# Interface.net
KiCad netlist of a schematic drawn in Altium Designer
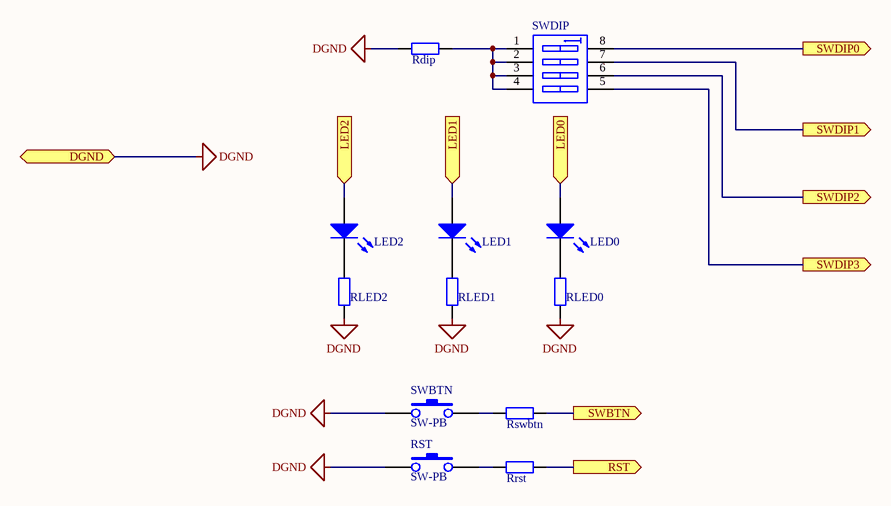
[diagram p0: Interface.SchDoc]

(export (version "E")
  (design (tool "Eeschema 10.0.6"))
  (components
    (comp (ref "LED0")
      (value "LTST-C170KGKT")
      (footprint "ECE-LED2012-0805SM")
      (description "LED GREEN CLEAR 0805 SM")
      (libsource (lib "Diodes$") (part "DIO000104"))
    )
    (comp (ref "LED1")
      (value "LTST-C170KAKT")
      (footprint "ECE-LED2012-0805SM")
      (description "LED RED ORANGE CLEAR 0805 SMD")
      (libsource (lib "Diodes$") (part "DIO000105"))
    )
    (comp (ref "LED2")
      (value "LTST-C170KAKT")
      (footprint "ECE-LED2012-0805SM")
      (description "LED RED ORANGE CLEAR 0805 SMD")
      (libsource (lib "Diodes$") (part "DIO000105"))
    )
    (comp (ref "Rdip")
      (value "1K")
      (footprint "ECE-RESC2012-0805SM")
      (description "RES CER 1K 2012 SM")
      (libsource (lib "Resistors$") (part "RES000538"))
    )
    (comp (ref "RLED0")
      (value "270R")
      (footprint "ECE-RESC1608-0603SM")
      (description "RES CER 270R 1608 SM")
      (libsource (lib "Resistors$") (part "RES000131"))
    )
    (comp (ref "RLED1")
      (value "270R")
      (footprint "ECE-RESC1608-0603SM")
      (description "RES CER 270R 1608 SM")
      (libsource (lib "Resistors$") (part "RES000131"))
    )
    (comp (ref "RLED2")
      (value "270R")
      (footprint "ECE-RESC1608-0603SM")
      (description "RES CER 270R 1608 SM")
      (libsource (lib "Resistors$") (part "RES000131"))
    )
    (comp (ref "Rrst")
      (value "1K")
      (footprint "ECE-RESC1608-0603SM")
      (description "RES CER 1K 1608 SM")
      (libsource (lib "Resistors$") (part "RES000138"))
    )
    (comp (ref "RST")
      (value "SW-PB")
      (footprint "SW-PB")
      (description "Push Button Switch")
      (libsource (lib "COMSYS301_2013") (part "SW-PB"))
    )
    (comp (ref "Rswbtn")
      (value "1K")
      (footprint "ECE-RESC1608-0603SM")
      (description "RES CER 1K 1608 SM")
      (libsource (lib "Resistors$") (part "RES000138"))
    )
    (comp (ref "SWBTN")
      (value "SW-PB")
      (footprint "SW-PB")
      (description "Push Button Switch")
      (libsource (lib "COMSYS301_2013") (part "SW-PB"))
    )
    (comp (ref "SWDIP") (value "*") (footprint "ECE-DIP8") (libsource (lib "ECE-Old") (part "Switch-DIP8")))
  )
  (nets
    (net (code "1") (name "/LED0") (class "Default")
      (node (ref "LED0") (pin "1") (pinfunction "A_1") (pintype "passive"))
    )
    (net (code "2") (name "/LED1") (class "Default")
      (node (ref "LED1") (pin "1") (pinfunction "A_1") (pintype "passive"))
    )
    (net (code "3") (name "/LED2") (class "Default")
      (node (ref "LED2") (pin "1") (pinfunction "A_1") (pintype "passive"))
    )
    (net (code "4") (name "/RST") (class "Default")
      (node (ref "Rrst") (pin "2") (pinfunction "2_2") (pintype "passive"))
    )
    (net (code "5") (name "/SWBTN") (class "Default")
      (node (ref "Rswbtn") (pin "2") (pinfunction "2_2") (pintype "passive"))
    )
    (net (code "6") (name "/SWDIP0") (class "Default")
      (node (ref "SWDIP") (pin "8") (pinfunction "B1_8") (pintype "passive"))
    )
    (net (code "7") (name "/SWDIP1") (class "Default")
      (node (ref "SWDIP") (pin "7") (pinfunction "B2_7") (pintype "passive"))
    )
    (net (code "8") (name "/SWDIP2") (class "Default")
      (node (ref "SWDIP") (pin "6") (pinfunction "B3_6") (pintype "passive"))
    )
    (net (code "9") (name "/SWDIP3") (class "Default")
      (node (ref "SWDIP") (pin "5") (pinfunction "B4_5") (pintype "passive"))
    )
    (net (code "10") (name "DGND") (class "Default")
      (node (ref "RLED0") (pin "1") (pinfunction "1_1") (pintype "passive"))
      (node (ref "RLED1") (pin "1") (pinfunction "1_1") (pintype "passive"))
      (node (ref "RLED2") (pin "1") (pinfunction "1_1") (pintype "passive"))
      (node (ref "RST") (pin "1") (pinfunction "1_1") (pintype "passive"))
      (node (ref "Rdip") (pin "1") (pinfunction "1_1") (pintype "passive"))
      (node (ref "SWBTN") (pin "1") (pinfunction "1_1") (pintype "passive"))
    )
    (net (code "11") (name "Net-(LED0-K)") (class "Default")
      (node (ref "LED0") (pin "2") (pinfunction "K_2") (pintype "passive"))
      (node (ref "RLED0") (pin "2") (pinfunction "2_2") (pintype "passive"))
    )
    (net (code "12") (name "Net-(LED1-K)") (class "Default")
      (node (ref "LED1") (pin "2") (pinfunction "K_2") (pintype "passive"))
      (node (ref "RLED1") (pin "2") (pinfunction "2_2") (pintype "passive"))
    )
    (net (code "13") (name "Net-(LED2-K)") (class "Default")
      (node (ref "LED2") (pin "2") (pinfunction "K_2") (pintype "passive"))
      (node (ref "RLED2") (pin "2") (pinfunction "2_2") (pintype "passive"))
    )
    (net (code "14") (name "Net-(RST-Pad2)") (class "Default")
      (node (ref "RST") (pin "2") (pinfunction "2_2") (pintype "passive"))
      (node (ref "Rrst") (pin "1") (pinfunction "1_1") (pintype "passive"))
    )
    (net (code "15") (name "Net-(Rswbtn-Pad1)") (class "Default")
      (node (ref "Rswbtn") (pin "1") (pinfunction "1_1") (pintype "passive"))
      (node (ref "SWBTN") (pin "2") (pinfunction "2_2") (pintype "passive"))
    )
    (net (code "16") (name "Net-(SWDIP-A1)") (class "Default")
      (node (ref "Rdip") (pin "2") (pinfunction "2_2") (pintype "passive"))
      (node (ref "SWDIP") (pin "1") (pinfunction "A1_1") (pintype "passive"))
      (node (ref "SWDIP") (pin "2") (pinfunction "A2_2") (pintype "passive"))
      (node (ref "SWDIP") (pin "3") (pinfunction "A3_3") (pintype "passive"))
      (node (ref "SWDIP") (pin "4") (pinfunction "A4_4") (pintype "passive"))
    )
  )
)
